# step-dir.net
KiCad netlist of a schematic drawn in Altium Designer
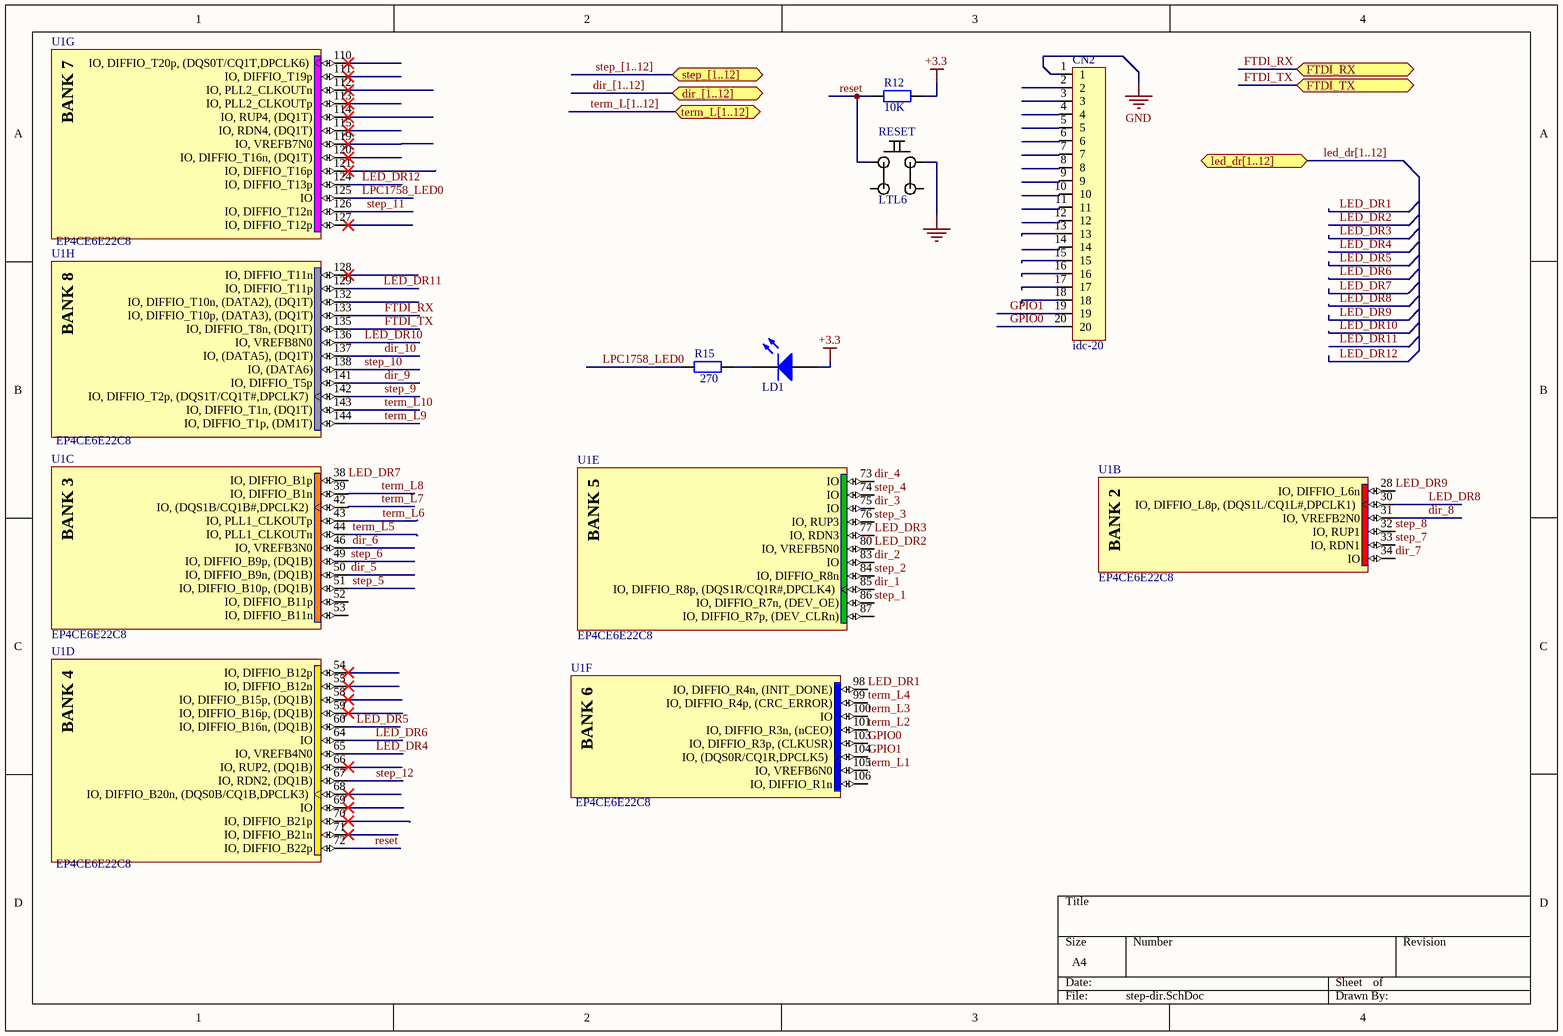
[diagram p0: step-dir.SchDoc]

(export (version "E")
  (design (tool "Eeschema 10.0.6"))
  (components
    (comp (ref "CN2") (value "idc-20") (footprint "IDC2.54-V20C") (libsource (lib "Schlib1") (part "idc-20")))
    (comp (ref "LD1")
      (value "chip led")
      (footprint "RESC2012M")
      (libsource (lib "Schlib1") (part "chip led"))
    )
    (comp (ref "R12")
      (value "10K")
      (footprint "RESC2012M")
      (description "Resistor")
      (fields (field (name "Comment") "Res2") (field (name "PUBLISHER") "Altium Limited"))
      (libsource (lib "Miscellaneous Devices") (part "Res2"))
    )
    (comp (ref "R15")
      (value "270")
      (footprint "RESC2012M")
      (description "Resistor")
      (fields (field (name "Comment") "Res2") (field (name "PUBLISHER") "Altium Limited"))
      (libsource (lib "") (part "Res2_1"))
    )
    (comp (ref "RESET")
      (value "LTL6")
      (footprint "BUTTON - LTL6")
      (libsource (lib "Schlib1") (part "chip button LTL6"))
    )
    (comp (ref "U1")
      (value "EP4CE6E22C8")
      (footprint "EQFP144_M")
      (description "Cyclone IV Family FPGA, 2V Core, 91 I/O Pins, 2 PLLs, 144-Pin QFP, Speed Grade 8, Commercial Grade")
      (fields (field (name "PUBLISHER") "Altium Limited"))
      (libsource (lib "Altera Cyclone IV E") (part "EP4CE6E22C8"))
    )
  )
  (nets
    (net (code "17") (name "+3.3") (class "Default")
      (node (ref "LD1") (pin "1") (pinfunction "A_1") (pintype "passive"))
      (node (ref "R12") (pin "2") (pinfunction "2_2") (pintype "passive"))
    )
    (net (code "18") (name "/FTDI_RX") (class "Default")
      (node (ref "U1") (pin "133") (pinfunction "IO,_DIFFIO_T10p,_(DATA3),_(DQ1T)_133") (pintype "bidirectional"))
    )
    (net (code "19") (name "/FTDI_TX") (class "Default")
      (node (ref "U1") (pin "135") (pinfunction "IO,_DIFFIO_T8n,_(DQ1T)_135") (pintype "bidirectional"))
    )
    (net (code "20") (name "/GPIO0") (class "Default")
      (node (ref "CN2") (pin "20") (pinfunction "20_20") (pintype "passive"))
      (node (ref "U1") (pin "103") (pinfunction "IO,_DIFFIO_R3p,_(CLKUSR)_103") (pintype "bidirectional"))
    )
    (net (code "21") (name "/GPIO1") (class "Default")
      (node (ref "CN2") (pin "19") (pinfunction "19_19") (pintype "passive"))
      (node (ref "U1") (pin "104") (pinfunction "IO,_(DQS0R/CQ1R,DPCLK5)_104") (pintype "bidirectional"))
    )
    (net (code "22") (name "/LED_DR1") (class "Default")
      (node (ref "U1") (pin "98") (pinfunction "IO,_DIFFIO_R4n,_(INIT_DONE)_98") (pintype "bidirectional"))
    )
    (net (code "23") (name "/LED_DR2") (class "Default")
      (node (ref "U1") (pin "80") (pinfunction "IO,_VREFB5N0_80") (pintype "bidirectional"))
    )
    (net (code "24") (name "/LED_DR3") (class "Default")
      (node (ref "U1") (pin "77") (pinfunction "IO,_RDN3_77") (pintype "bidirectional"))
    )
    (net (code "25") (name "/LED_DR4") (class "Default")
      (node (ref "U1") (pin "65") (pinfunction "IO,_VREFB4N0_65") (pintype "bidirectional"))
    )
    (net (code "26") (name "/LED_DR5") (class "Default")
      (node (ref "U1") (pin "60") (pinfunction "IO,_DIFFIO_B16n,_(DQ1B)_60") (pintype "bidirectional"))
    )
    (net (code "27") (name "/LED_DR6") (class "Default")
      (node (ref "U1") (pin "64") (pinfunction "IO_64") (pintype "bidirectional"))
    )
    (net (code "28") (name "/LED_DR7") (class "Default")
      (node (ref "U1") (pin "38") (pinfunction "IO,_DIFFIO_B1p_38") (pintype "bidirectional"))
    )
    (net (code "29") (name "/LED_DR8") (class "Default")
      (node (ref "U1") (pin "30") (pinfunction "IO,_DIFFIO_L8p,_(DQS1L/CQ1L#,DPCLK1)_30") (pintype "bidirectional"))
    )
    (net (code "30") (name "/LED_DR9") (class "Default")
      (node (ref "U1") (pin "28") (pinfunction "IO,_DIFFIO_L6n_28") (pintype "bidirectional"))
    )
    (net (code "31") (name "/LED_DR10") (class "Default")
      (node (ref "U1") (pin "136") (pinfunction "IO,_VREFB8N0_136") (pintype "bidirectional"))
    )
    (net (code "32") (name "/LED_DR11") (class "Default")
      (node (ref "U1") (pin "129") (pinfunction "IO,_DIFFIO_T11p_129") (pintype "bidirectional"))
    )
    (net (code "33") (name "/LED_DR12") (class "Default")
      (node (ref "U1") (pin "124") (pinfunction "IO,_DIFFIO_T13p_124") (pintype "bidirectional"))
    )
    (net (code "34") (name "/LPC1758_LED0") (class "Default")
      (node (ref "R15") (pin "1") (pinfunction "1_1") (pintype "passive"))
      (node (ref "U1") (pin "125") (pinfunction "IO_125") (pintype "bidirectional"))
    )
    (net (code "35") (name "/dir_1") (class "Default")
      (node (ref "U1") (pin "85") (pinfunction "IO,_DIFFIO_R8p,_(DQS1R/CQ1R#,DPCLK4)_85") (pintype "bidirectional"))
    )
    (net (code "36") (name "/dir_2") (class "Default")
      (node (ref "U1") (pin "83") (pinfunction "IO_83") (pintype "bidirectional"))
    )
    (net (code "37") (name "/dir_3") (class "Default")
      (node (ref "U1") (pin "75") (pinfunction "IO_75") (pintype "bidirectional"))
    )
    (net (code "38") (name "/dir_4") (class "Default")
      (node (ref "U1") (pin "73") (pinfunction "IO_73") (pintype "bidirectional"))
    )
    (net (code "39") (name "/dir_5") (class "Default")
      (node (ref "U1") (pin "50") (pinfunction "IO,_DIFFIO_B9n,_(DQ1B)_50") (pintype "bidirectional"))
    )
    (net (code "40") (name "/dir_6") (class "Default")
      (node (ref "U1") (pin "46") (pinfunction "IO,_VREFB3N0_46") (pintype "bidirectional"))
    )
    (net (code "41") (name "/dir_7") (class "Default")
      (node (ref "U1") (pin "34") (pinfunction "IO_34") (pintype "bidirectional"))
    )
    (net (code "42") (name "/dir_8") (class "Default")
      (node (ref "U1") (pin "31") (pinfunction "IO,_VREFB2N0_31") (pintype "bidirectional"))
    )
    (net (code "43") (name "/dir_9") (class "Default")
      (node (ref "U1") (pin "141") (pinfunction "IO,_DIFFIO_T5p_141") (pintype "bidirectional"))
    )
    (net (code "44") (name "/dir_10") (class "Default")
      (node (ref "U1") (pin "137") (pinfunction "IO,_(DATA5),_(DQ1T)_137") (pintype "bidirectional"))
    )
    (net (code "47") (name "/reset") (class "Default")
      (node (ref "R12") (pin "1") (pinfunction "1_1") (pintype "passive"))
      (node (ref "RESET") (pin "3") (pinfunction "3_3") (pintype "passive"))
      (node (ref "U1") (pin "72") (pinfunction "IO,_DIFFIO_B22p_72") (pintype "bidirectional"))
    )
    (net (code "48") (name "/step_1") (class "Default")
      (node (ref "U1") (pin "86") (pinfunction "IO,_DIFFIO_R7n,_(DEV_OE)_86") (pintype "bidirectional"))
    )
    (net (code "49") (name "/step_2") (class "Default")
      (node (ref "U1") (pin "84") (pinfunction "IO,_DIFFIO_R8n_84") (pintype "bidirectional"))
    )
    (net (code "50") (name "/step_3") (class "Default")
      (node (ref "U1") (pin "76") (pinfunction "IO,_RUP3_76") (pintype "bidirectional"))
    )
    (net (code "51") (name "/step_4") (class "Default")
      (node (ref "U1") (pin "74") (pinfunction "IO_74") (pintype "bidirectional"))
    )
    (net (code "52") (name "/step_5") (class "Default")
      (node (ref "U1") (pin "51") (pinfunction "IO,_DIFFIO_B10p,_(DQ1B)_51") (pintype "bidirectional"))
    )
    (net (code "53") (name "/step_6") (class "Default")
      (node (ref "U1") (pin "49") (pinfunction "IO,_DIFFIO_B9p,_(DQ1B)_49") (pintype "bidirectional"))
    )
    (net (code "54") (name "/step_7") (class "Default")
      (node (ref "U1") (pin "33") (pinfunction "IO,_RDN1_33") (pintype "bidirectional"))
    )
    (net (code "55") (name "/step_8") (class "Default")
      (node (ref "U1") (pin "32") (pinfunction "IO,_RUP1_32") (pintype "bidirectional"))
    )
    (net (code "56") (name "/step_9") (class "Default")
      (node (ref "U1") (pin "142") (pinfunction "IO,_DIFFIO_T2p,_(DQS1T/CQ1T#,DPCLK7)_142") (pintype "bidirectional"))
    )
    (net (code "57") (name "/step_10") (class "Default")
      (node (ref "U1") (pin "138") (pinfunction "IO,_(DATA6)_138") (pintype "bidirectional"))
    )
    (net (code "58") (name "/step_11") (class "Default")
      (node (ref "U1") (pin "126") (pinfunction "IO,_DIFFIO_T12n_126") (pintype "bidirectional"))
    )
    (net (code "59") (name "/step_12") (class "Default")
      (node (ref "U1") (pin "67") (pinfunction "IO,_RDN2,_(DQ1B)_67") (pintype "bidirectional"))
    )
    (net (code "61") (name "/term_L1") (class "Default")
      (node (ref "U1") (pin "105") (pinfunction "IO,_VREFB6N0_105") (pintype "bidirectional"))
    )
    (net (code "62") (name "/term_L2") (class "Default")
      (node (ref "U1") (pin "101") (pinfunction "IO,_DIFFIO_R3n,_(nCEO)_101") (pintype "bidirectional"))
    )
    (net (code "63") (name "/term_L3") (class "Default")
      (node (ref "U1") (pin "100") (pinfunction "IO_100") (pintype "bidirectional"))
    )
    (net (code "64") (name "/term_L4") (class "Default")
      (node (ref "U1") (pin "99") (pinfunction "IO,_DIFFIO_R4p,_(CRC_ERROR)_99") (pintype "bidirectional"))
    )
    (net (code "65") (name "/term_L5") (class "Default")
      (node (ref "U1") (pin "44") (pinfunction "IO,_PLL1_CLKOUTn_44") (pintype "bidirectional"))
    )
    (net (code "66") (name "/term_L6") (class "Default")
      (node (ref "U1") (pin "43") (pinfunction "IO,_PLL1_CLKOUTp_43") (pintype "bidirectional"))
    )
    (net (code "67") (name "/term_L7") (class "Default")
      (node (ref "U1") (pin "42") (pinfunction "IO,_(DQS1B/CQ1B#,DPCLK2)_42") (pintype "bidirectional"))
    )
    (net (code "68") (name "/term_L8") (class "Default")
      (node (ref "U1") (pin "39") (pinfunction "IO,_DIFFIO_B1n_39") (pintype "bidirectional"))
    )
    (net (code "69") (name "/term_L9") (class "Default")
      (node (ref "U1") (pin "144") (pinfunction "IO,_DIFFIO_T1p,_(DM1T)_144") (pintype "bidirectional"))
    )
    (net (code "70") (name "/term_L10") (class "Default")
      (node (ref "U1") (pin "143") (pinfunction "IO,_DIFFIO_T1n,_(DQ1T)_143") (pintype "bidirectional"))
    )
    (net (code "72") (name "GND") (class "Default")
      (node (ref "CN2") (pin "1") (pinfunction "1_1") (pintype "passive"))
      (node (ref "RESET") (pin "1") (pinfunction "1_1") (pintype "passive"))
    )
    (net (code "73") (name "Net-(LD1-K)") (class "Default")
      (node (ref "LD1") (pin "2") (pinfunction "K_2") (pintype "passive"))
      (node (ref "R15") (pin "2") (pinfunction "2_2") (pintype "passive"))
    )
    (net (code "74") (name "unconnected-(CN2-Pad2)") (class "Default")
      (node (ref "CN2") (pin "2") (pinfunction "2_2") (pintype "passive"))
    )
    (net (code "75") (name "unconnected-(CN2-Pad3)") (class "Default")
      (node (ref "CN2") (pin "3") (pinfunction "3_3") (pintype "passive"))
    )
    (net (code "76") (name "unconnected-(CN2-Pad4)") (class "Default")
      (node (ref "CN2") (pin "4") (pinfunction "4_4") (pintype "passive"))
    )
    (net (code "77") (name "unconnected-(CN2-Pad5)") (class "Default")
      (node (ref "CN2") (pin "5") (pinfunction "5_5") (pintype "passive"))
    )
    (net (code "78") (name "unconnected-(CN2-Pad6)") (class "Default")
      (node (ref "CN2") (pin "6") (pinfunction "6_6") (pintype "passive"))
    )
    (net (code "79") (name "unconnected-(CN2-Pad7)") (class "Default")
      (node (ref "CN2") (pin "7") (pinfunction "7_7") (pintype "passive"))
    )
    (net (code "80") (name "unconnected-(CN2-Pad8)") (class "Default")
      (node (ref "CN2") (pin "8") (pinfunction "8_8") (pintype "passive"))
    )
    (net (code "81") (name "unconnected-(CN2-Pad9)") (class "Default")
      (node (ref "CN2") (pin "9") (pinfunction "9_9") (pintype "passive"))
    )
    (net (code "82") (name "unconnected-(CN2-Pad10)") (class "Default")
      (node (ref "CN2") (pin "10") (pinfunction "10_10") (pintype "passive"))
    )
    (net (code "83") (name "unconnected-(CN2-Pad11)") (class "Default")
      (node (ref "CN2") (pin "11") (pinfunction "11_11") (pintype "passive"))
    )
    (net (code "84") (name "unconnected-(CN2-Pad12)") (class "Default")
      (node (ref "CN2") (pin "12") (pinfunction "12_12") (pintype "passive"))
    )
    (net (code "85") (name "unconnected-(CN2-Pad13)") (class "Default")
      (node (ref "CN2") (pin "13") (pinfunction "13_13") (pintype "passive"))
    )
    (net (code "86") (name "unconnected-(CN2-Pad14)") (class "Default")
      (node (ref "CN2") (pin "14") (pinfunction "14_14") (pintype "passive"))
    )
    (net (code "87") (name "unconnected-(CN2-Pad15)") (class "Default")
      (node (ref "CN2") (pin "15") (pinfunction "15_15") (pintype "passive"))
    )
    (net (code "88") (name "unconnected-(CN2-Pad16)") (class "Default")
      (node (ref "CN2") (pin "16") (pinfunction "16_16") (pintype "passive"))
    )
    (net (code "89") (name "unconnected-(CN2-Pad17)") (class "Default")
      (node (ref "CN2") (pin "17") (pinfunction "17_17") (pintype "passive"))
    )
    (net (code "90") (name "unconnected-(CN2-Pad18)") (class "Default")
      (node (ref "CN2") (pin "18") (pinfunction "18_18") (pintype "passive"))
    )
    (net (code "91") (name "unconnected-(RESET-Pad2)") (class "Default")
      (node (ref "RESET") (pin "2") (pinfunction "2_2") (pintype "passive"))
    )
    (net (code "92") (name "unconnected-(RESET-Pad4)") (class "Default")
      (node (ref "RESET") (pin "4") (pinfunction "4_4") (pintype "passive"))
    )
    (net (code "93") (name "unconnected-(U1C-IO,_DIFFIO_B11n-Pad53)") (class "Default")
      (node (ref "U1") (pin "53") (pinfunction "IO,_DIFFIO_B11n_53") (pintype "bidirectional"))
    )
    (net (code "94") (name "unconnected-(U1C-IO,_DIFFIO_B11p-Pad52)") (class "Default")
      (node (ref "U1") (pin "52") (pinfunction "IO,_DIFFIO_B11p_52") (pintype "bidirectional"))
    )
    (net (code "95") (name "unconnected-(U1D-IO,_DIFFIO_B12n-Pad55)") (class "Default")
      (node (ref "U1") (pin "55") (pinfunction "IO,_DIFFIO_B12n_55") (pintype "bidirectional+no_connect"))
    )
    (net (code "96") (name "unconnected-(U1D-IO,_DIFFIO_B12p-Pad54)") (class "Default")
      (node (ref "U1") (pin "54") (pinfunction "IO,_DIFFIO_B12p_54") (pintype "bidirectional+no_connect"))
    )
    (net (code "97") (name "unconnected-(U1D-IO,_DIFFIO_B15p,_(DQ1B)-Pad58)") (class "Default")
      (node (ref "U1") (pin "58") (pinfunction "IO,_DIFFIO_B15p,_(DQ1B)_58") (pintype "bidirectional+no_connect"))
    )
    (net (code "98") (name "unconnected-(U1D-IO,_DIFFIO_B16p,_(DQ1B)-Pad59)") (class "Default")
      (node (ref "U1") (pin "59") (pinfunction "IO,_DIFFIO_B16p,_(DQ1B)_59") (pintype "bidirectional+no_connect"))
    )
    (net (code "99") (name "unconnected-(U1D-IO,_DIFFIO_B20n,_(DQS0B{slash}CQ1B,DPCLK3)-Pad68)") (class "Default")
      (node (ref "U1") (pin "68") (pinfunction "IO,_DIFFIO_B20n,_(DQS0B/CQ1B,DPCLK3)_68") (pintype "bidirectional+no_connect"))
    )
    (net (code "100") (name "unconnected-(U1D-IO,_DIFFIO_B21n-Pad71)") (class "Default")
      (node (ref "U1") (pin "71") (pinfunction "IO,_DIFFIO_B21n_71") (pintype "bidirectional+no_connect"))
    )
    (net (code "101") (name "unconnected-(U1D-IO,_DIFFIO_B21p-Pad70)") (class "Default")
      (node (ref "U1") (pin "70") (pinfunction "IO,_DIFFIO_B21p_70") (pintype "bidirectional+no_connect"))
    )
    (net (code "102") (name "unconnected-(U1D-IO,_RUP2,_(DQ1B)-Pad66)") (class "Default")
      (node (ref "U1") (pin "66") (pinfunction "IO,_RUP2,_(DQ1B)_66") (pintype "bidirectional+no_connect"))
    )
    (net (code "103") (name "unconnected-(U1D-IO-Pad69)") (class "Default")
      (node (ref "U1") (pin "69") (pinfunction "IO_69") (pintype "bidirectional+no_connect"))
    )
    (net (code "104") (name "unconnected-(U1E-IO,_DIFFIO_R7p,_(DEV_CLRn)-Pad87)") (class "Default")
      (node (ref "U1") (pin "87") (pinfunction "IO,_DIFFIO_R7p,_(DEV_CLRn)_87") (pintype "bidirectional"))
    )
    (net (code "105") (name "unconnected-(U1F-IO,_DIFFIO_R1n-Pad106)") (class "Default")
      (node (ref "U1") (pin "106") (pinfunction "IO,_DIFFIO_R1n_106") (pintype "bidirectional"))
    )
    (net (code "106") (name "unconnected-(U1G-IO,_DIFFIO_T12p-Pad127)") (class "Default")
      (node (ref "U1") (pin "127") (pinfunction "IO,_DIFFIO_T12p_127") (pintype "bidirectional+no_connect"))
    )
    (net (code "107") (name "unconnected-(U1G-IO,_DIFFIO_T16n,_(DQ1T)-Pad120)") (class "Default")
      (node (ref "U1") (pin "120") (pinfunction "IO,_DIFFIO_T16n,_(DQ1T)_120") (pintype "bidirectional+no_connect"))
    )
    (net (code "108") (name "unconnected-(U1G-IO,_DIFFIO_T16p-Pad121)") (class "Default")
      (node (ref "U1") (pin "121") (pinfunction "IO,_DIFFIO_T16p_121") (pintype "bidirectional+no_connect"))
    )
    (net (code "109") (name "unconnected-(U1G-IO,_DIFFIO_T19p-Pad111)") (class "Default")
      (node (ref "U1") (pin "111") (pinfunction "IO,_DIFFIO_T19p_111") (pintype "bidirectional+no_connect"))
    )
    (net (code "110") (name "unconnected-(U1G-IO,_DIFFIO_T20p,_(DQS0T{slash}CQ1T,DPCLK6)-Pad110)") (class "Default")
      (node (ref "U1") (pin "110") (pinfunction "IO,_DIFFIO_T20p,_(DQS0T/CQ1T,DPCLK6)_110") (pintype "bidirectional+no_connect"))
    )
    (net (code "111") (name "unconnected-(U1G-IO,_PLL2_CLKOUTn-Pad112)") (class "Default")
      (node (ref "U1") (pin "112") (pinfunction "IO,_PLL2_CLKOUTn_112") (pintype "bidirectional+no_connect"))
    )
    (net (code "112") (name "unconnected-(U1G-IO,_PLL2_CLKOUTp-Pad113)") (class "Default")
      (node (ref "U1") (pin "113") (pinfunction "IO,_PLL2_CLKOUTp_113") (pintype "bidirectional+no_connect"))
    )
    (net (code "113") (name "unconnected-(U1G-IO,_RDN4,_(DQ1T)-Pad115)") (class "Default")
      (node (ref "U1") (pin "115") (pinfunction "IO,_RDN4,_(DQ1T)_115") (pintype "bidirectional+no_connect"))
    )
    (net (code "114") (name "unconnected-(U1G-IO,_RUP4,_(DQ1T)-Pad114)") (class "Default")
      (node (ref "U1") (pin "114") (pinfunction "IO,_RUP4,_(DQ1T)_114") (pintype "bidirectional+no_connect"))
    )
    (net (code "115") (name "unconnected-(U1G-IO,_VREFB7N0-Pad119)") (class "Default")
      (node (ref "U1") (pin "119") (pinfunction "IO,_VREFB7N0_119") (pintype "bidirectional+no_connect"))
    )
    (net (code "116") (name "unconnected-(U1H-IO,_DIFFIO_T10n,_(DATA2),_(DQ1T)-Pad132)") (class "Default")
      (node (ref "U1") (pin "132") (pinfunction "IO,_DIFFIO_T10n,_(DATA2),_(DQ1T)_132") (pintype "bidirectional"))
    )
    (net (code "117") (name "unconnected-(U1H-IO,_DIFFIO_T11n-Pad128)") (class "Default")
      (node (ref "U1") (pin "128") (pinfunction "IO,_DIFFIO_T11n_128") (pintype "bidirectional+no_connect"))
    )
  )
)
